# 6coils.net
KiCad netlist of a schematic drawn in EasyEDA
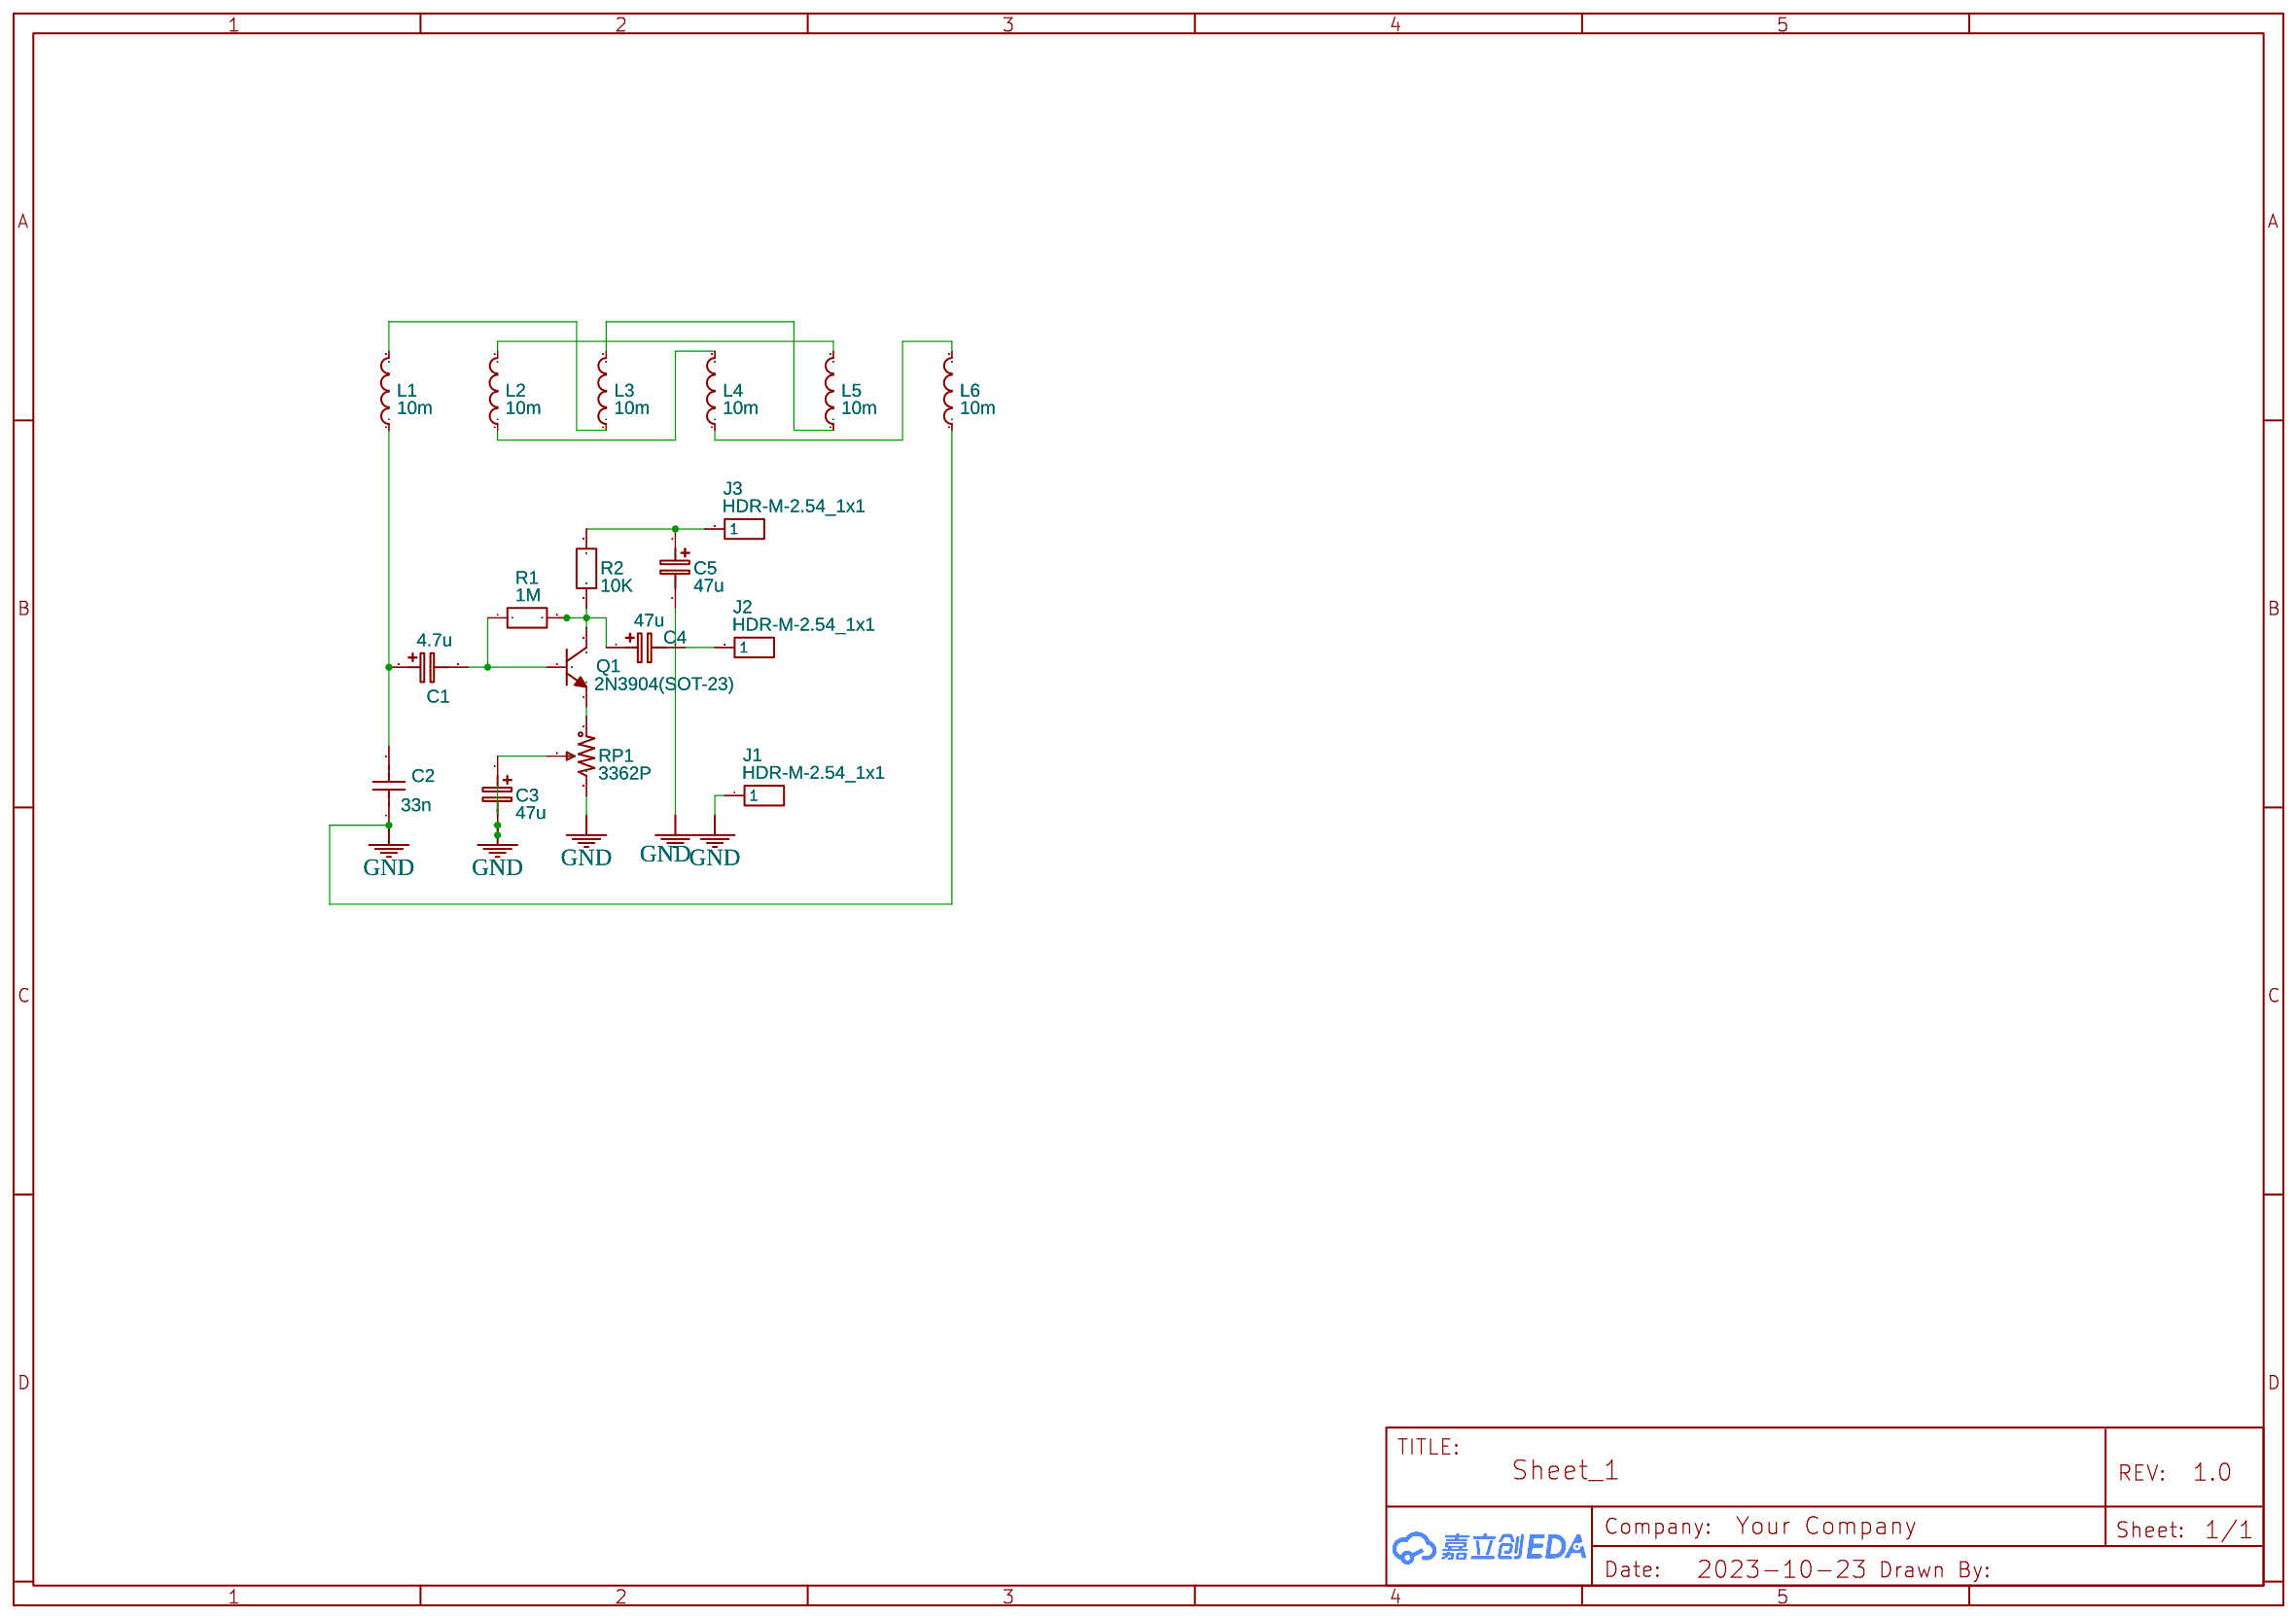
[diagram p0: schematic sheet]

(export (version "E")
  (design (tool "Eeschema 10.0.6"))
  (components
    (comp (ref "C1") (value "4.7u") (libsource (lib "") (part "C_Tan_SMD_A_EU_2")))
    (comp (ref "C2") (value "33n") (libsource (lib "") (part "C_0603_US")))
    (comp (ref "C3") (value "47u") (libsource (lib "") (part "C_Tan_SMD_A_EU_3")))
    (comp (ref "C4") (value "47u") (libsource (lib "") (part "C_Tan_SMD_A_EU")))
    (comp (ref "C5") (value "47u") (libsource (lib "") (part "C_Tan_SMD_A_EU_1")))
    (comp (ref "J1")
      (value "HDR-M-2.54_1x1")
      (fields (field (name "BOM_Supplier Part") "C81276"))
      (libsource (lib "") (part "HDR-M-2.54_1x1"))
    )
    (comp (ref "J2")
      (value "HDR-M-2.54_1x1")
      (fields (field (name "BOM_Supplier Part") "C81276"))
      (libsource (lib "") (part "HDR-M-2.54_1x1"))
    )
    (comp (ref "J3")
      (value "HDR-M-2.54_1x1")
      (fields (field (name "BOM_Supplier Part") "C81276"))
      (libsource (lib "") (part "HDR-M-2.54_1x1"))
    )
    (comp (ref "L1") (value "10m") (libsource (lib "") (part "L0603_US")))
    (comp (ref "L2") (value "10m") (libsource (lib "") (part "L0603_US")))
    (comp (ref "L3") (value "10m") (libsource (lib "") (part "L0603_US")))
    (comp (ref "L4") (value "10m") (libsource (lib "") (part "L0603_US")))
    (comp (ref "L5") (value "10m") (libsource (lib "") (part "L0603_US")))
    (comp (ref "L6") (value "10m") (libsource (lib "") (part "L0603_US")))
    (comp (ref "Q1")
      (value "2N3904(SOT-23)")
      (fields
        (field (name "BOM_Manufacturer Part") "2n3904S-RTK/PS")
        (field (name "BOM_Supplier Part") "C18536")
      )
      (libsource (lib "") (part "2N3904(SOT-23)"))
    )
    (comp (ref "R1") (value "1M") (libsource (lib "") (part "R_0603_EU_1")))
    (comp (ref "R2") (value "10K") (libsource (lib "") (part "R_0603_EU")))
    (comp (ref "RP1") (value "3362P") (libsource (lib "") (part "R_3386P_US")))
  )
  (nets
    (net (code "1") (name "GND") (class "Default")
      (node (ref "C2") (pin "1") (pinfunction "1_1") (pintype "unspecified"))
      (node (ref "C3") (pin "2") (pinfunction "2_2") (pintype "unspecified"))
      (node (ref "C5") (pin "2") (pinfunction "2_2") (pintype "unspecified"))
      (node (ref "J1") (pin "1") (pinfunction "1_1") (pintype "input"))
      (node (ref "L6") (pin "1") (pinfunction "1_1") (pintype "unspecified"))
      (node (ref "RP1") (pin "3") (pinfunction "3_3") (pintype "unspecified"))
    )
    (net (code "2") (name "Net-(C1-Pad1)") (class "Default")
      (node (ref "C1") (pin "1") (pinfunction "1_1") (pintype "unspecified"))
      (node (ref "C2") (pin "2") (pinfunction "2_2") (pintype "unspecified"))
      (node (ref "L1") (pin "1") (pinfunction "1_1") (pintype "unspecified"))
    )
    (net (code "3") (name "Net-(C3-Pad1)") (class "Default")
      (node (ref "C3") (pin "1") (pinfunction "1_1") (pintype "unspecified"))
      (node (ref "RP1") (pin "2") (pinfunction "2_2") (pintype "unspecified"))
    )
    (net (code "4") (name "Net-(C4-Pad2)") (class "Default")
      (node (ref "C4") (pin "2") (pinfunction "2_2") (pintype "unspecified"))
      (node (ref "J2") (pin "1") (pinfunction "1_1") (pintype "input"))
    )
    (net (code "5") (name "Net-(C5-Pad1)") (class "Default")
      (node (ref "C5") (pin "1") (pinfunction "1_1") (pintype "unspecified"))
      (node (ref "J3") (pin "1") (pinfunction "1_1") (pintype "input"))
      (node (ref "R2") (pin "2") (pinfunction "2_2") (pintype "unspecified"))
    )
    (net (code "6") (name "Net-(L1-Pad2)") (class "Default")
      (node (ref "L1") (pin "2") (pinfunction "2_2") (pintype "unspecified"))
      (node (ref "L3") (pin "1") (pinfunction "1_1") (pintype "unspecified"))
    )
    (net (code "7") (name "Net-(L2-Pad1)") (class "Default")
      (node (ref "L2") (pin "1") (pinfunction "1_1") (pintype "unspecified"))
      (node (ref "L4") (pin "2") (pinfunction "2_2") (pintype "unspecified"))
    )
    (net (code "8") (name "Net-(L2-Pad2)") (class "Default")
      (node (ref "L2") (pin "2") (pinfunction "2_2") (pintype "unspecified"))
      (node (ref "L5") (pin "2") (pinfunction "2_2") (pintype "unspecified"))
    )
    (net (code "9") (name "Net-(L3-Pad2)") (class "Default")
      (node (ref "L3") (pin "2") (pinfunction "2_2") (pintype "unspecified"))
      (node (ref "L5") (pin "1") (pinfunction "1_1") (pintype "unspecified"))
    )
    (net (code "10") (name "Net-(L4-Pad1)") (class "Default")
      (node (ref "L4") (pin "1") (pinfunction "1_1") (pintype "unspecified"))
      (node (ref "L6") (pin "2") (pinfunction "2_2") (pintype "unspecified"))
    )
    (net (code "11") (name "Net-(Q1-B)") (class "Default")
      (node (ref "C1") (pin "2") (pinfunction "2_2") (pintype "unspecified"))
      (node (ref "Q1") (pin "2") (pinfunction "B_2") (pintype "input"))
      (node (ref "R1") (pin "1") (pinfunction "1_1") (pintype "unspecified"))
    )
    (net (code "12") (name "Net-(Q1-C)") (class "Default")
      (node (ref "C4") (pin "1") (pinfunction "1_1") (pintype "unspecified"))
      (node (ref "Q1") (pin "3") (pinfunction "C_3") (pintype "input"))
      (node (ref "R1") (pin "2") (pinfunction "2_2") (pintype "unspecified"))
      (node (ref "R2") (pin "1") (pinfunction "1_1") (pintype "unspecified"))
    )
    (net (code "13") (name "Net-(Q1-E)") (class "Default")
      (node (ref "Q1") (pin "1") (pinfunction "E_1") (pintype "input"))
      (node (ref "RP1") (pin "1") (pinfunction "1_1") (pintype "unspecified"))
    )
  )
)
